# design.net
KiCad netlist of a schematic drawn in Altium Designer
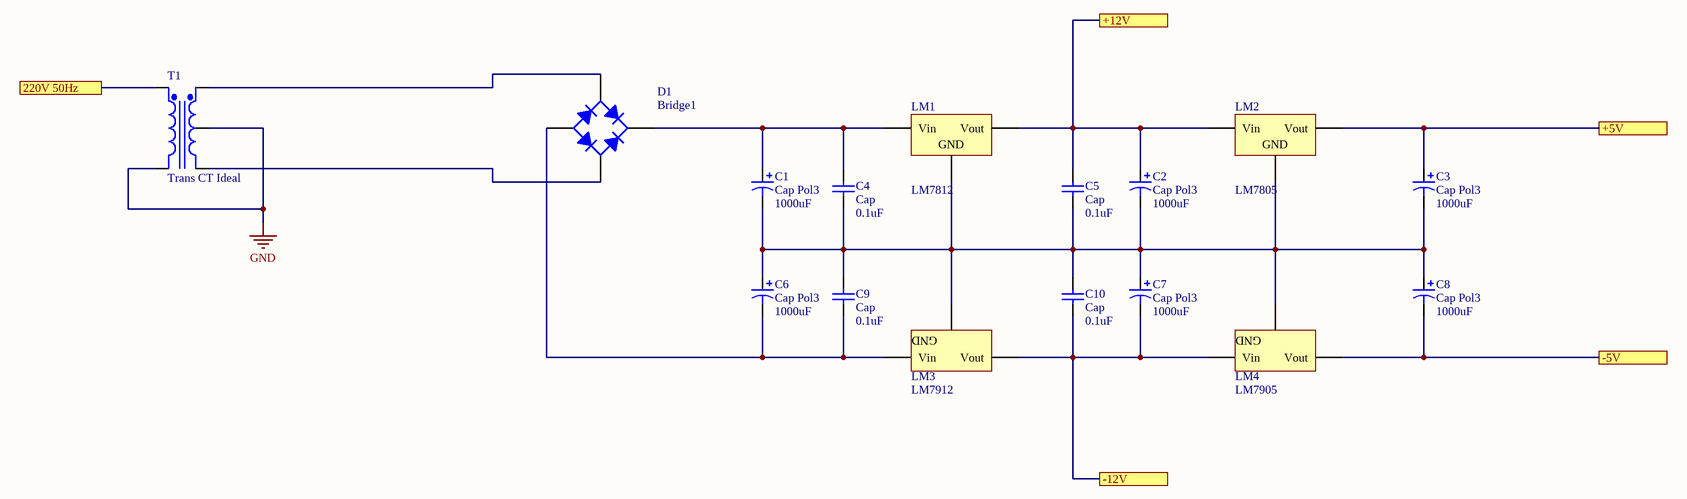
[diagram p0: 电源板原理图.SchDoc]

(export (version "E")
  (design (tool "Eeschema 10.0.6"))
  (components
    (comp (ref "C1")
      (value "Cap Pol3")
      (footprint "1812")
      (description "Polarized Capacitor (Surface Mount)")
      (fields (field (name "ALTIUM_VALUE") "1000uF") (field (name "PUBLISHER") "Altium Limited"))
      (libsource (lib "Miscellaneous Devices") (part "Cap Pol3"))
    )
    (comp (ref "C2")
      (value "Cap Pol3")
      (footprint "1812")
      (description "Polarized Capacitor (Surface Mount)")
      (fields (field (name "ALTIUM_VALUE") "1000uF") (field (name "PUBLISHER") "Altium Limited"))
      (libsource (lib "Miscellaneous Devices") (part "Cap Pol3"))
    )
    (comp (ref "C3")
      (value "Cap Pol3")
      (footprint "1812")
      (description "Polarized Capacitor (Surface Mount)")
      (fields (field (name "ALTIUM_VALUE") "1000uF") (field (name "PUBLISHER") "Altium Limited"))
      (libsource (lib "Miscellaneous Devices") (part "Cap Pol3"))
    )
    (comp (ref "C4")
      (value "Cap")
      (footprint "RAD-0.3")
      (description "Capacitor")
      (fields (field (name "ALTIUM_VALUE") "0.1uF") (field (name "PUBLISHER") "Altium Limited"))
      (libsource (lib "Miscellaneous Devices") (part "Cap"))
    )
    (comp (ref "C5")
      (value "Cap")
      (footprint "RAD-0.3")
      (description "Capacitor")
      (fields (field (name "ALTIUM_VALUE") "0.1uF") (field (name "PUBLISHER") "Altium Limited"))
      (libsource (lib "Miscellaneous Devices") (part "Cap"))
    )
    (comp (ref "C6")
      (value "Cap Pol3")
      (footprint "1812")
      (description "Polarized Capacitor (Surface Mount)")
      (fields (field (name "ALTIUM_VALUE") "1000uF") (field (name "PUBLISHER") "Altium Limited"))
      (libsource (lib "Miscellaneous Devices") (part "Cap Pol3"))
    )
    (comp (ref "C7")
      (value "Cap Pol3")
      (footprint "1812")
      (description "Polarized Capacitor (Surface Mount)")
      (fields (field (name "ALTIUM_VALUE") "1000uF") (field (name "PUBLISHER") "Altium Limited"))
      (libsource (lib "Miscellaneous Devices") (part "Cap Pol3"))
    )
    (comp (ref "C8")
      (value "Cap Pol3")
      (footprint "1812")
      (description "Polarized Capacitor (Surface Mount)")
      (fields (field (name "ALTIUM_VALUE") "1000uF") (field (name "PUBLISHER") "Altium Limited"))
      (libsource (lib "Miscellaneous Devices") (part "Cap Pol3"))
    )
    (comp (ref "C9")
      (value "Cap")
      (footprint "RAD-0.3")
      (description "Capacitor")
      (fields (field (name "ALTIUM_VALUE") "0.1uF") (field (name "PUBLISHER") "Altium Limited"))
      (libsource (lib "Miscellaneous Devices") (part "Cap"))
    )
    (comp (ref "C10")
      (value "Cap")
      (footprint "RAD-0.3")
      (description "Capacitor")
      (fields (field (name "ALTIUM_VALUE") "0.1uF") (field (name "PUBLISHER") "Altium Limited"))
      (libsource (lib "Miscellaneous Devices") (part "Cap"))
    )
    (comp (ref "D1")
      (value "Bridge1")
      (footprint "D-38")
      (description "Full Wave Diode Bridge")
      (fields (field (name "PUBLISHER") "Altium Limited"))
      (libsource (lib "Miscellaneous Devices") (part "Bridge1"))
    )
    (comp (ref "LM1")
      (value "LM7812")
      (footprint "D2PAK_L")
      (description "Voltage Regulator")
      (fields (field (name "PUBLISHER") "Altium Limited"))
      (libsource (lib "Miscellaneous Devices") (part "Volt Reg"))
    )
    (comp (ref "LM2")
      (value "LM7805")
      (footprint "D2PAK_L")
      (description "Voltage Regulator")
      (fields (field (name "PUBLISHER") "Altium Limited"))
      (libsource (lib "Miscellaneous Devices") (part "Volt Reg"))
    )
    (comp (ref "LM3")
      (value "LM7912")
      (footprint "D2PAK_L")
      (description "Voltage Regulator")
      (fields (field (name "PUBLISHER") "Altium Limited"))
      (libsource (lib "") (part "Volt Reg_1"))
    )
    (comp (ref "LM4")
      (value "LM7905")
      (footprint "D2PAK_L")
      (description "Voltage Regulator")
      (fields (field (name "PUBLISHER") "Altium Limited"))
      (libsource (lib "") (part "Volt Reg_1"))
    )
    (comp (ref "T1")
      (value "Trans CT Ideal")
      (footprint "TRF_5")
      (description "Center-Tapped Transformer (Ideal)")
      (fields (field (name "PUBLISHER") "Altium Limited"))
      (libsource (lib "Miscellaneous Devices") (part "Trans CT Ideal"))
    )
  )
  (nets
    (net (code "1") (name "/+5V") (class "Default")
      (node (ref "C3") (pin "1") (pinfunction "1_1") (pintype "passive"))
      (node (ref "LM2") (pin "3") (pinfunction "Vout_3") (pintype "passive"))
    )
    (net (code "2") (name "/+12V") (class "Default")
      (node (ref "C2") (pin "1") (pinfunction "1_1") (pintype "passive"))
      (node (ref "C5") (pin "2") (pinfunction "2_2") (pintype "passive"))
      (node (ref "LM1") (pin "3") (pinfunction "Vout_3") (pintype "passive"))
      (node (ref "LM2") (pin "1") (pinfunction "Vin_1") (pintype "passive"))
    )
    (net (code "3") (name "/-5V") (class "Default")
      (node (ref "C8") (pin "2") (pinfunction "2_2") (pintype "passive"))
      (node (ref "LM4") (pin "3") (pinfunction "Vout_3") (pintype "passive"))
    )
    (net (code "4") (name "/-12V") (class "Default")
      (node (ref "C10") (pin "1") (pinfunction "1_1") (pintype "passive"))
      (node (ref "C7") (pin "2") (pinfunction "2_2") (pintype "passive"))
      (node (ref "LM3") (pin "3") (pinfunction "Vout_3") (pintype "passive"))
      (node (ref "LM4") (pin "1") (pinfunction "Vin_1") (pintype "passive"))
    )
    (net (code "5") (name "/220V 50Hz") (class "Default")
      (node (ref "T1") (pin "1") (pinfunction "Pri+_1") (pintype "passive"))
    )
    (net (code "6") (name "GND") (class "Default")
      (node (ref "T1") (pin "2") (pinfunction "Pri-_2") (pintype "passive"))
      (node (ref "T1") (pin "4") (pinfunction "SecCT_4") (pintype "passive"))
    )
    (net (code "7") (name "Net-(D1-A)") (class "Default")
      (node (ref "C6") (pin "2") (pinfunction "2_2") (pintype "passive"))
      (node (ref "C9") (pin "1") (pinfunction "1_1") (pintype "passive"))
      (node (ref "D1") (pin "3") (pinfunction "A_3") (pintype "passive"))
      (node (ref "LM3") (pin "1") (pinfunction "Vin_1") (pintype "passive"))
    )
    (net (code "8") (name "Net-(D1-K)") (class "Default")
      (node (ref "C1") (pin "1") (pinfunction "1_1") (pintype "passive"))
      (node (ref "C4") (pin "2") (pinfunction "2_2") (pintype "passive"))
      (node (ref "D1") (pin "1") (pinfunction "K_1") (pintype "passive"))
      (node (ref "LM1") (pin "1") (pinfunction "Vin_1") (pintype "passive"))
    )
    (net (code "9") (name "Net-(LM1-GND)") (class "Default")
      (node (ref "C1") (pin "2") (pinfunction "2_2") (pintype "passive"))
      (node (ref "C10") (pin "2") (pinfunction "2_2") (pintype "passive"))
      (node (ref "C2") (pin "2") (pinfunction "2_2") (pintype "passive"))
      (node (ref "C3") (pin "2") (pinfunction "2_2") (pintype "passive"))
      (node (ref "C4") (pin "1") (pinfunction "1_1") (pintype "passive"))
      (node (ref "C5") (pin "1") (pinfunction "1_1") (pintype "passive"))
      (node (ref "C6") (pin "1") (pinfunction "1_1") (pintype "passive"))
      (node (ref "C7") (pin "1") (pinfunction "1_1") (pintype "passive"))
      (node (ref "C8") (pin "1") (pinfunction "1_1") (pintype "passive"))
      (node (ref "C9") (pin "2") (pinfunction "2_2") (pintype "passive"))
      (node (ref "LM1") (pin "2") (pinfunction "GND_2") (pintype "passive"))
      (node (ref "LM2") (pin "2") (pinfunction "GND_2") (pintype "passive"))
      (node (ref "LM3") (pin "2") (pinfunction "GND_2") (pintype "passive"))
      (node (ref "LM4") (pin "2") (pinfunction "GND_2") (pintype "passive"))
    )
    (net (code "10") (name "Net-(T1-Sec+)") (class "Default")
      (node (ref "D1") (pin "4") (pinfunction "C_4") (pintype "passive"))
      (node (ref "T1") (pin "3") (pinfunction "Sec+_3") (pintype "passive"))
    )
    (net (code "11") (name "Net-(T1-Sec-)") (class "Default")
      (node (ref "D1") (pin "2") (pinfunction "C_2") (pintype "passive"))
      (node (ref "T1") (pin "5") (pinfunction "Sec-_5") (pintype "passive"))
    )
  )
)
